# blitzbox.net
KiCad netlist of a schematic drawn in EAGLE
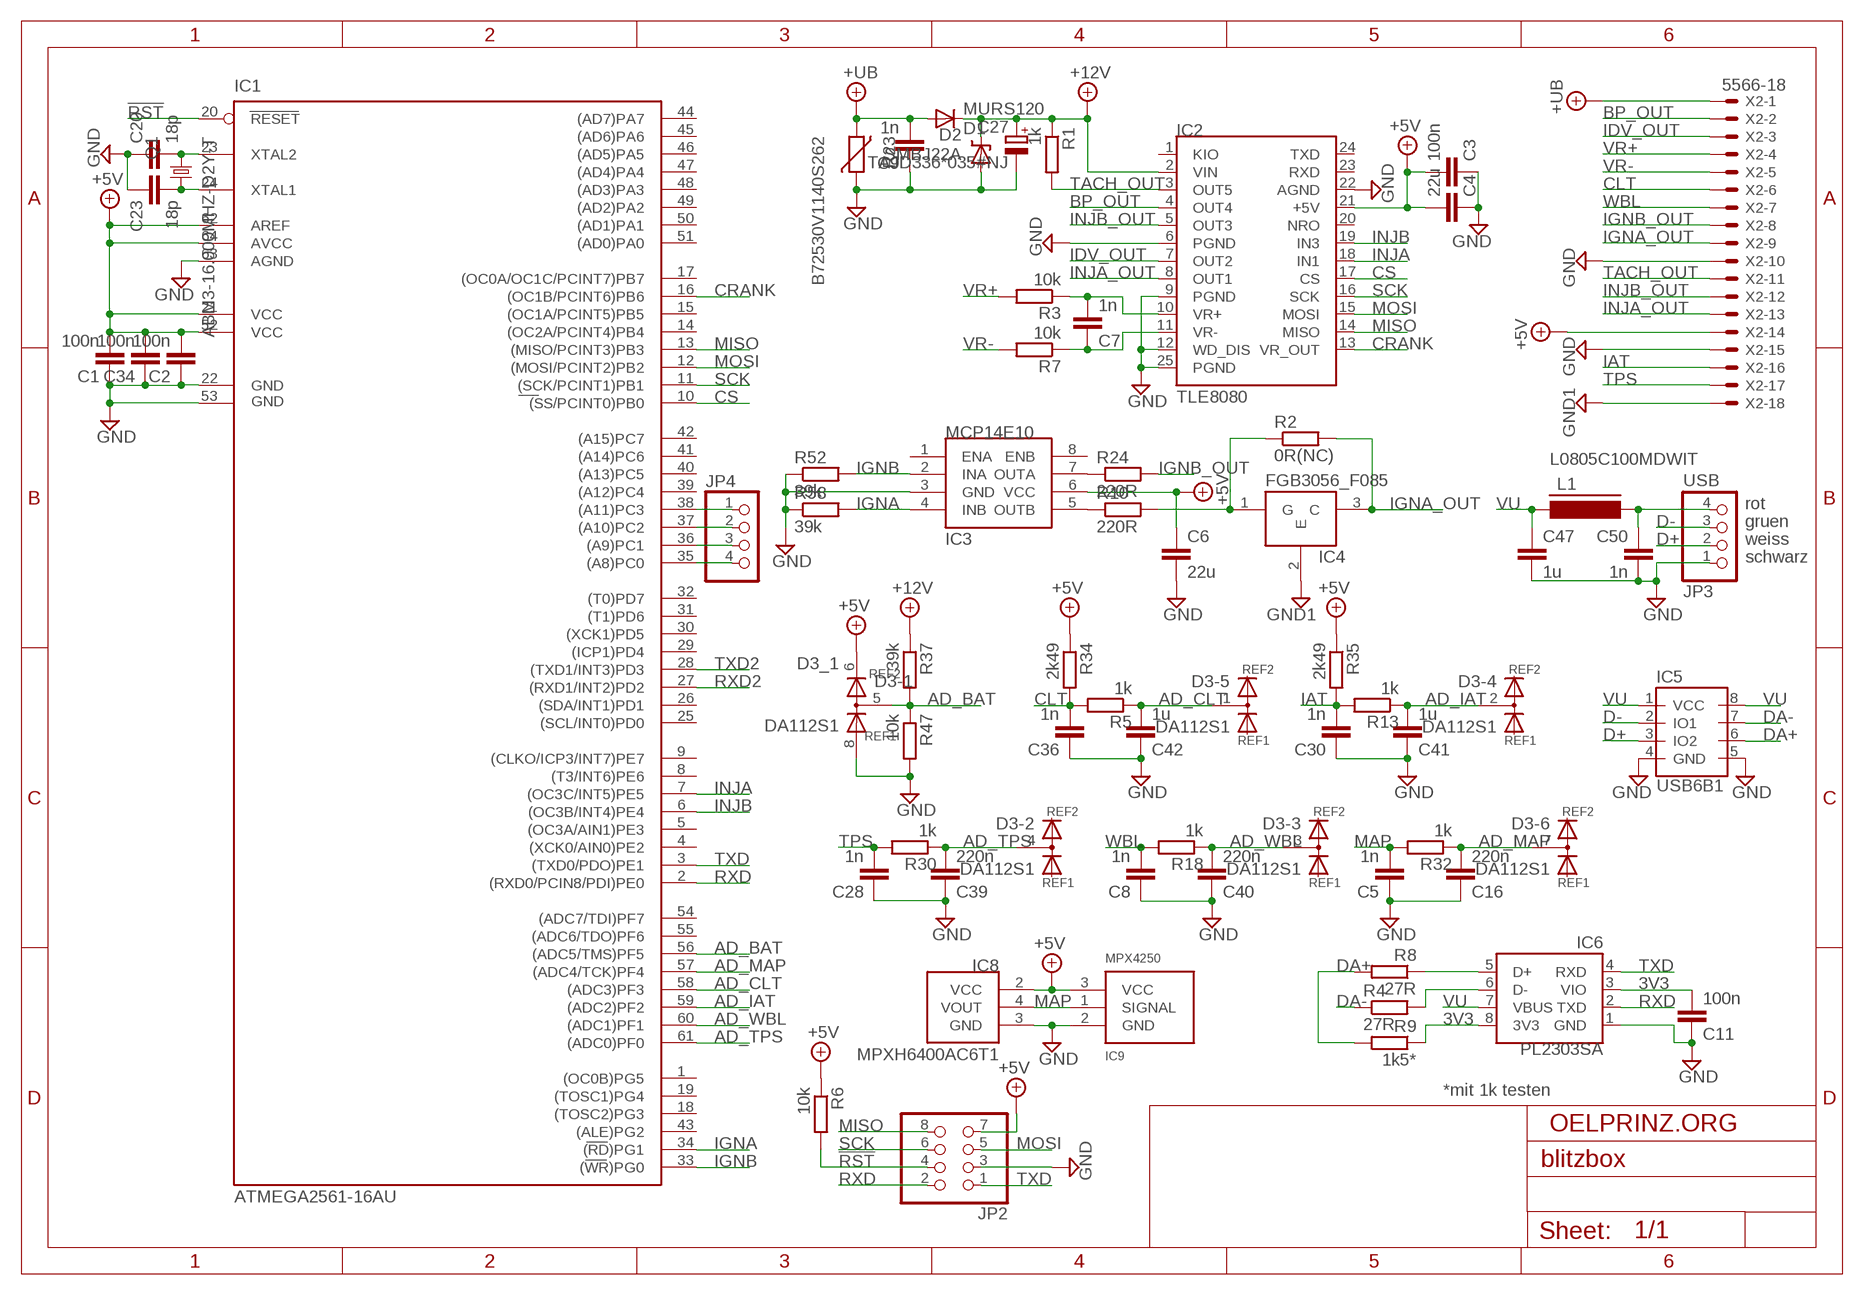
[diagram p0: schematic, sheet 1]

(export (version "E")
  (design (tool "Eeschema 10.0.6"))
  (components
    (comp (ref "C1")
      (value "100n")
      (footprint "eagle-import:C0805")
      (libsource (lib "eagle-import") (part "C-EUC0805"))
    )
    (comp (ref "C2")
      (value "100n")
      (footprint "eagle-import:C0805")
      (libsource (lib "eagle-import") (part "C-EUC0805"))
    )
    (comp (ref "C3")
      (value "100n")
      (footprint "eagle-import:C0805")
      (libsource (lib "eagle-import") (part "C-EUC0805"))
    )
    (comp (ref "C4")
      (value "22u")
      (footprint "eagle-import:C1210")
      (libsource (lib "eagle-import") (part "C-EUC1210"))
    )
    (comp (ref "C5")
      (value "1n")
      (footprint "eagle-import:C0805")
      (libsource (lib "eagle-import") (part "C-EUC0805"))
    )
    (comp (ref "C6")
      (value "22u")
      (footprint "eagle-import:C1206")
      (libsource (lib "eagle-import") (part "C-EUC1206"))
    )
    (comp (ref "C7")
      (value "1n")
      (footprint "eagle-import:C0805")
      (libsource (lib "eagle-import") (part "C-EUC0805"))
    )
    (comp (ref "C8")
      (value "1n")
      (footprint "eagle-import:C0805")
      (libsource (lib "eagle-import") (part "C-EUC0805"))
    )
    (comp (ref "C9")
      (value "1n")
      (footprint "eagle-import:C0805")
      (libsource (lib "eagle-import") (part "C-EUC0805"))
    )
    (comp (ref "C11")
      (value "100n")
      (footprint "eagle-import:C0805")
      (libsource (lib "eagle-import") (part "C-EUC0805"))
    )
    (comp (ref "C16")
      (value "220n")
      (footprint "eagle-import:C0805")
      (libsource (lib "eagle-import") (part "C-EUC0805"))
    )
    (comp (ref "C20")
      (value "18p")
      (footprint "eagle-import:C0805")
      (libsource (lib "eagle-import") (part "C-EUC0805"))
    )
    (comp (ref "C23")
      (value "18p")
      (footprint "eagle-import:C0805")
      (libsource (lib "eagle-import") (part "C-EUC0805"))
    )
    (comp (ref "C27")
      (value "TAJD336*035#NJ")
      (footprint "eagle-import:SMC_D")
      (libsource (lib "eagle-import") (part "CPOL-EUSMCD"))
    )
    (comp (ref "C28")
      (value "1n")
      (footprint "eagle-import:C0805")
      (libsource (lib "eagle-import") (part "C-EUC0805"))
    )
    (comp (ref "C30")
      (value "1n")
      (footprint "eagle-import:C0805")
      (libsource (lib "eagle-import") (part "C-EUC0805"))
    )
    (comp (ref "C34")
      (value "100n")
      (footprint "eagle-import:C0805")
      (libsource (lib "eagle-import") (part "C-EUC0805"))
    )
    (comp (ref "C36")
      (value "1n")
      (footprint "eagle-import:C0805")
      (libsource (lib "eagle-import") (part "C-EUC0805"))
    )
    (comp (ref "C39")
      (value "220n")
      (footprint "eagle-import:C0805")
      (libsource (lib "eagle-import") (part "C-EUC0805"))
    )
    (comp (ref "C40")
      (value "220n")
      (footprint "eagle-import:C0805")
      (libsource (lib "eagle-import") (part "C-EUC0805"))
    )
    (comp (ref "C41")
      (value "1u")
      (footprint "eagle-import:C0805")
      (libsource (lib "eagle-import") (part "C-EUC0805"))
    )
    (comp (ref "C42")
      (value "1u")
      (footprint "eagle-import:C0805")
      (libsource (lib "eagle-import") (part "C-EUC0805"))
    )
    (comp (ref "C47")
      (value "1u")
      (footprint "eagle-import:C0805")
      (libsource (lib "eagle-import") (part "C-EUC0805"))
    )
    (comp (ref "C50")
      (value "1n")
      (footprint "eagle-import:C0805")
      (libsource (lib "eagle-import") (part "C-EUC0805"))
    )
    (comp (ref "D1")
      (value "MURS120")
      (footprint "eagle-import:MURS120")
      (libsource (lib "eagle-import") (part "MURS120"))
    )
    (comp (ref "D2")
      (value "SMBJ22A")
      (footprint "eagle-import:SMBJ")
      (libsource (lib "eagle-import") (part "SUPPRESSOR-SMBJ"))
    )
    (comp (ref "D3")
      (value "DA112S1")
      (footprint "eagle-import:SO08")
      (fields (field (name "MF") "Arrow Electronics"))
      (libsource (lib "eagle-import") (part "DA112S1"))
    )
    (comp (ref "IC1")
      (value "ATMEGA2561-16AU")
      (footprint "eagle-import:TQFP64")
      (libsource (lib "eagle-import") (part "ATMEGA2561AU-16"))
    )
    (comp (ref "IC2")
      (value "TLE8080")
      (footprint "eagle-import:TLE8080")
      (libsource (lib "eagle-import") (part "TLE8080"))
    )
    (comp (ref "IC3")
      (value "MCP14E10")
      (footprint "eagle-import:SO-08")
      (libsource (lib "eagle-import") (part "MCP14E10"))
    )
    (comp (ref "IC4")
      (value "FGB3056_F085")
      (footprint "eagle-import:TO263")
      (libsource (lib "eagle-import") (part "FGB3056_F085"))
    )
    (comp (ref "IC5")
      (value "USB6B1")
      (footprint "eagle-import:SO08")
      (libsource (lib "eagle-import") (part "USB6B1"))
    )
    (comp (ref "IC6")
      (value "PL2303SA")
      (footprint "eagle-import:SO-08")
      (libsource (lib "eagle-import") (part "PL2303SA"))
    )
    (comp (ref "IC8")
      (value "MPXH6400AC6T1")
      (footprint "eagle-import:MPXH6400")
      (libsource (lib "eagle-import") (part "MPXH6400"))
    )
    (comp (ref "IC9")
      (value "MPX4250")
      (footprint "eagle-import:MPX4250")
      (libsource (lib "eagle-import") (part "MPX4250"))
    )
    (comp (ref "JP2")
      (value "PINHD-2X4")
      (footprint "eagle-import:2X04")
      (libsource (lib "eagle-import") (part "PINHD-2X4"))
    )
    (comp (ref "JP3")
      (value "USB")
      (footprint "eagle-import:1X04")
      (libsource (lib "eagle-import") (part "PINHD-1X4"))
    )
    (comp (ref "JP4")
      (value "PINHD-1X4")
      (footprint "eagle-import:1X04")
      (libsource (lib "eagle-import") (part "PINHD-1X4"))
    )
    (comp (ref "L1")
      (value "L0805C100MDWIT")
      (footprint "eagle-import:FB805")
      (libsource (lib "eagle-import") (part "FERRITE_BEAD805"))
    )
    (comp (ref "Q1")
      (value "ABM3-16.000MHZ-D2Y-T")
      (footprint "eagle-import:ABM3")
      (libsource (lib "eagle-import") (part "ABM3-8.000MHZ-D2Y-T"))
    )
    (comp (ref "R1")
      (value "1k")
      (footprint "eagle-import:R0805")
      (libsource (lib "eagle-import") (part "R-EU_R0805"))
    )
    (comp (ref "R2")
      (value "0R(NC)")
      (footprint "eagle-import:R0805")
      (libsource (lib "eagle-import") (part "R-EU_R0805"))
    )
    (comp (ref "R3")
      (value "10k")
      (footprint "eagle-import:R0805")
      (libsource (lib "eagle-import") (part "R-EU_R0805"))
    )
    (comp (ref "R4")
      (value "27R")
      (footprint "eagle-import:R0805")
      (libsource (lib "eagle-import") (part "R-EU_R0805"))
    )
    (comp (ref "R5")
      (value "1k")
      (footprint "eagle-import:R0805")
      (libsource (lib "eagle-import") (part "R-EU_R0805"))
    )
    (comp (ref "R6")
      (value "10k")
      (footprint "eagle-import:R0805")
      (libsource (lib "eagle-import") (part "R-EU_R0805"))
    )
    (comp (ref "R7")
      (value "10k")
      (footprint "eagle-import:R0805")
      (libsource (lib "eagle-import") (part "R-EU_R0805"))
    )
    (comp (ref "R8")
      (value "27R")
      (footprint "eagle-import:R0805")
      (libsource (lib "eagle-import") (part "R-EU_R0805"))
    )
    (comp (ref "R9")
      (value "1k5*")
      (footprint "eagle-import:R0805")
      (libsource (lib "eagle-import") (part "R-EU_R0805"))
    )
    (comp (ref "R10")
      (value "220R")
      (footprint "eagle-import:R0805")
      (libsource (lib "eagle-import") (part "R-EU_R0805"))
    )
    (comp (ref "R13")
      (value "1k")
      (footprint "eagle-import:R0805")
      (libsource (lib "eagle-import") (part "R-EU_R0805"))
    )
    (comp (ref "R18")
      (value "1k")
      (footprint "eagle-import:R0805")
      (libsource (lib "eagle-import") (part "R-EU_R0805"))
    )
    (comp (ref "R23")
      (value "B72530V1140S262")
      (footprint "eagle-import:CT_CN1210")
      (libsource (lib "eagle-import") (part "VARISTORCN1210"))
    )
    (comp (ref "R24")
      (value "220R")
      (footprint "eagle-import:R0805")
      (libsource (lib "eagle-import") (part "R-EU_R0805"))
    )
    (comp (ref "R30")
      (value "1k")
      (footprint "eagle-import:R0805")
      (libsource (lib "eagle-import") (part "R-EU_R0805"))
    )
    (comp (ref "R32")
      (value "1k")
      (footprint "eagle-import:R0805")
      (libsource (lib "eagle-import") (part "R-EU_R0805"))
    )
    (comp (ref "R34")
      (value "2k49")
      (footprint "eagle-import:R0805")
      (libsource (lib "eagle-import") (part "R-EU_R0805"))
    )
    (comp (ref "R35")
      (value "2k49")
      (footprint "eagle-import:R0805")
      (libsource (lib "eagle-import") (part "R-EU_R0805"))
    )
    (comp (ref "R37")
      (value "39k")
      (footprint "eagle-import:R0805")
      (libsource (lib "eagle-import") (part "R-EU_R0805"))
    )
    (comp (ref "R47")
      (value "10k")
      (footprint "eagle-import:R0805")
      (libsource (lib "eagle-import") (part "R-EU_R0805"))
    )
    (comp (ref "R52")
      (value "39k")
      (footprint "eagle-import:R0805")
      (libsource (lib "eagle-import") (part "R-EU_R0805"))
    )
    (comp (ref "R58")
      (value "39k")
      (footprint "eagle-import:R0805")
      (libsource (lib "eagle-import") (part "R-EU_R0805"))
    )
    (comp (ref "X2")
      (value "5566-18")
      (footprint "eagle-import:5566-18")
      (libsource (lib "eagle-import") (part "5566-18"))
    )
  )
  (nets
    (net (code "1") (name "+5V") (class "Default")
      (node (ref "C1") (pin "2") (pinfunction "2_2") (pintype "passive"))
      (node (ref "C2") (pin "2") (pinfunction "2_2") (pintype "passive"))
      (node (ref "C3") (pin "2") (pinfunction "2_2") (pintype "passive"))
      (node (ref "C34") (pin "2") (pinfunction "2_2") (pintype "passive"))
      (node (ref "C4") (pin "2") (pinfunction "2_2") (pintype "passive"))
      (node (ref "C6") (pin "1") (pinfunction "1_1") (pintype "passive"))
      (node (ref "D3") (pin "6") (pinfunction "REF2_6") (pintype "passive"))
      (node (ref "IC1") (pin "21") (pinfunction "VCC_21") (pintype "power_in"))
      (node (ref "IC1") (pin "52") (pinfunction "VCC1_52") (pintype "power_in"))
      (node (ref "IC1") (pin "62") (pinfunction "AREF_62") (pintype "bidirectional"))
      (node (ref "IC1") (pin "64") (pinfunction "AVCC_64") (pintype "power_in"))
      (node (ref "IC2") (pin "21") (pinfunction "+5V_21") (pintype "bidirectional"))
      (node (ref "IC3") (pin "6") (pinfunction "VCC_6") (pintype "bidirectional"))
      (node (ref "IC8") (pin "2") (pinfunction "VCC_2") (pintype "bidirectional"))
      (node (ref "IC9") (pin "3") (pinfunction "VCC_3") (pintype "bidirectional"))
      (node (ref "JP2") (pin "7") (pinfunction "7_7") (pintype "passive"))
      (node (ref "R34") (pin "1") (pinfunction "1_1") (pintype "passive"))
      (node (ref "R35") (pin "1") (pinfunction "1_1") (pintype "passive"))
      (node (ref "R6") (pin "1") (pinfunction "1_1") (pintype "passive"))
      (node (ref "X2") (pin "14") (pinfunction "S_14") (pintype "passive"))
    )
    (net (code "2") (name "+12V") (class "Default")
      (node (ref "C27") (pin "+") (pinfunction "+_+") (pintype "passive"))
      (node (ref "D1") (pin "2") (pinfunction "C_2") (pintype "passive"))
      (node (ref "D2") (pin "C") (pinfunction "C_C") (pintype "passive"))
      (node (ref "IC2") (pin "2") (pinfunction "VIN_2") (pintype "bidirectional"))
      (node (ref "R1") (pin "1") (pinfunction "1_1") (pintype "passive"))
      (node (ref "R37") (pin "1") (pinfunction "1_1") (pintype "passive"))
    )
    (net (code "3") (name "+UB") (class "Default")
      (node (ref "C9") (pin "2") (pinfunction "2_2") (pintype "passive"))
      (node (ref "D1") (pin "1") (pinfunction "A_1") (pintype "passive"))
      (node (ref "R23") (pin "2") (pinfunction "2_2") (pintype "passive"))
      (node (ref "X2") (pin "1") (pinfunction "S_1") (pintype "passive"))
    )
    (net (code "4") (name "/3V3") (class "Default")
      (node (ref "C11") (pin "2") (pinfunction "2_2") (pintype "passive"))
      (node (ref "IC6") (pin "3") (pinfunction "VIO_3") (pintype "bidirectional"))
      (node (ref "IC6") (pin "8") (pinfunction "3V3_8") (pintype "bidirectional"))
      (node (ref "R9") (pin "1") (pinfunction "1_1") (pintype "passive"))
    )
    (net (code "5") (name "/AD_BAT") (class "Default")
      (node (ref "D3") (pin "5") (pinfunction "K_5") (pintype "passive"))
      (node (ref "IC1") (pin "56") (pinfunction "(ADC5/TMS)PF5_56") (pintype "bidirectional"))
      (node (ref "R37") (pin "2") (pinfunction "2_2") (pintype "passive"))
      (node (ref "R47") (pin "1") (pinfunction "1_1") (pintype "passive"))
    )
    (net (code "6") (name "/AD_CLT") (class "Default")
      (node (ref "C42") (pin "2") (pinfunction "2_2") (pintype "passive"))
      (node (ref "D3") (pin "1") (pinfunction "K_1") (pintype "passive"))
      (node (ref "IC1") (pin "58") (pinfunction "(ADC3)PF3_58") (pintype "bidirectional"))
      (node (ref "R5") (pin "1") (pinfunction "1_1") (pintype "passive"))
    )
    (net (code "7") (name "/AD_IAT") (class "Default")
      (node (ref "C41") (pin "2") (pinfunction "2_2") (pintype "passive"))
      (node (ref "D3") (pin "2") (pinfunction "K_2") (pintype "passive"))
      (node (ref "IC1") (pin "59") (pinfunction "(ADC2)PF2_59") (pintype "bidirectional"))
      (node (ref "R13") (pin "1") (pinfunction "1_1") (pintype "passive"))
    )
    (net (code "8") (name "/AD_MAP") (class "Default")
      (node (ref "C16") (pin "2") (pinfunction "2_2") (pintype "passive"))
      (node (ref "D3") (pin "7") (pinfunction "K_7") (pintype "passive"))
      (node (ref "IC1") (pin "57") (pinfunction "(ADC4/TCK)PF4_57") (pintype "bidirectional"))
      (node (ref "R32") (pin "1") (pinfunction "1_1") (pintype "passive"))
    )
    (net (code "9") (name "/AD_TPS") (class "Default")
      (node (ref "C39") (pin "2") (pinfunction "2_2") (pintype "passive"))
      (node (ref "D3") (pin "4") (pinfunction "K_4") (pintype "passive"))
      (node (ref "IC1") (pin "61") (pinfunction "(ADC0)PF0_61") (pintype "bidirectional"))
      (node (ref "R30") (pin "1") (pinfunction "1_1") (pintype "passive"))
    )
    (net (code "10") (name "/AD_WBL") (class "Default")
      (node (ref "C40") (pin "2") (pinfunction "2_2") (pintype "passive"))
      (node (ref "D3") (pin "3") (pinfunction "K_3") (pintype "passive"))
      (node (ref "IC1") (pin "60") (pinfunction "(ADC1)PF1_60") (pintype "bidirectional"))
      (node (ref "R18") (pin "1") (pinfunction "1_1") (pintype "passive"))
    )
    (net (code "11") (name "/BP_OUT") (class "Default")
      (node (ref "IC2") (pin "4") (pinfunction "OUT4_4") (pintype "bidirectional"))
      (node (ref "X2") (pin "2") (pinfunction "S_2") (pintype "passive"))
    )
    (net (code "12") (name "/CLT") (class "Default")
      (node (ref "C36") (pin "2") (pinfunction "2_2") (pintype "passive"))
      (node (ref "R34") (pin "2") (pinfunction "2_2") (pintype "passive"))
      (node (ref "R5") (pin "2") (pinfunction "2_2") (pintype "passive"))
      (node (ref "X2") (pin "6") (pinfunction "S_6") (pintype "passive"))
    )
    (net (code "13") (name "/CRANK") (class "Default")
      (node (ref "IC1") (pin "16") (pinfunction "(OC1B/PCINT6)PB6_16") (pintype "bidirectional"))
      (node (ref "IC2") (pin "13") (pinfunction "VR_OUT_13") (pintype "bidirectional"))
    )
    (net (code "14") (name "/CS") (class "Default")
      (node (ref "IC1") (pin "10") (pinfunction "(SS/PCINT0)PB0_10") (pintype "bidirectional"))
      (node (ref "IC2") (pin "17") (pinfunction "CS_17") (pintype "bidirectional"))
    )
    (net (code "15") (name "/D+") (class "Default")
      (node (ref "IC5") (pin "3") (pinfunction "IO2_3") (pintype "bidirectional"))
      (node (ref "JP3") (pin "2") (pinfunction "2_2") (pintype "passive"))
    )
    (net (code "16") (name "/D-") (class "Default")
      (node (ref "IC5") (pin "2") (pinfunction "IO1_2") (pintype "bidirectional"))
      (node (ref "JP3") (pin "3") (pinfunction "3_3") (pintype "passive"))
    )
    (net (code "17") (name "/DA+") (class "Default")
      (node (ref "IC5") (pin "6") (pinfunction "IO2_6") (pintype "bidirectional"))
      (node (ref "R8") (pin "2") (pinfunction "2_2") (pintype "passive"))
      (node (ref "R9") (pin "2") (pinfunction "2_2") (pintype "passive"))
    )
    (net (code "18") (name "/DA-") (class "Default")
      (node (ref "IC5") (pin "7") (pinfunction "IO1_7") (pintype "bidirectional"))
      (node (ref "R4") (pin "1") (pinfunction "1_1") (pintype "passive"))
    )
    (net (code "19") (name "/IAT") (class "Default")
      (node (ref "C30") (pin "2") (pinfunction "2_2") (pintype "passive"))
      (node (ref "R13") (pin "2") (pinfunction "2_2") (pintype "passive"))
      (node (ref "R35") (pin "2") (pinfunction "2_2") (pintype "passive"))
      (node (ref "X2") (pin "16") (pinfunction "S_16") (pintype "passive"))
    )
    (net (code "20") (name "/IDV_OUT") (class "Default")
      (node (ref "IC2") (pin "7") (pinfunction "OUT2_7") (pintype "bidirectional"))
      (node (ref "X2") (pin "3") (pinfunction "S_3") (pintype "passive"))
    )
    (net (code "21") (name "/IGNA") (class "Default")
      (node (ref "IC1") (pin "34") (pinfunction "(RD)PG1_34") (pintype "bidirectional"))
      (node (ref "IC3") (pin "4") (pinfunction "INB_4") (pintype "bidirectional"))
      (node (ref "R58") (pin "2") (pinfunction "2_2") (pintype "passive"))
    )
    (net (code "22") (name "/IGNA_OUT") (class "Default")
      (node (ref "IC4") (pin "3") (pinfunction "C_3") (pintype "bidirectional"))
      (node (ref "R2") (pin "2") (pinfunction "2_2") (pintype "passive"))
      (node (ref "X2") (pin "9") (pinfunction "S_9") (pintype "passive"))
    )
    (net (code "23") (name "/IGNB") (class "Default")
      (node (ref "IC1") (pin "33") (pinfunction "(WR)PG0_33") (pintype "bidirectional"))
      (node (ref "IC3") (pin "2") (pinfunction "INA_2") (pintype "bidirectional"))
      (node (ref "R52") (pin "2") (pinfunction "2_2") (pintype "passive"))
    )
    (net (code "24") (name "/IGNB_OUT") (class "Default")
      (node (ref "R24") (pin "2") (pinfunction "2_2") (pintype "passive"))
      (node (ref "X2") (pin "8") (pinfunction "S_8") (pintype "passive"))
    )
    (net (code "25") (name "/INJA") (class "Default")
      (node (ref "IC1") (pin "7") (pinfunction "(OC3C/INT5)PE5_7") (pintype "bidirectional"))
      (node (ref "IC2") (pin "18") (pinfunction "IN1_18") (pintype "bidirectional"))
    )
    (net (code "26") (name "/INJA_OUT") (class "Default")
      (node (ref "IC2") (pin "8") (pinfunction "OUT1_8") (pintype "bidirectional"))
      (node (ref "X2") (pin "13") (pinfunction "S_13") (pintype "passive"))
    )
    (net (code "27") (name "/INJB") (class "Default")
      (node (ref "IC1") (pin "6") (pinfunction "(OC3B/INT4)PE4_6") (pintype "bidirectional"))
      (node (ref "IC2") (pin "19") (pinfunction "IN3_19") (pintype "bidirectional"))
    )
    (net (code "28") (name "/INJB_OUT") (class "Default")
      (node (ref "IC2") (pin "5") (pinfunction "OUT3_5") (pintype "bidirectional"))
      (node (ref "X2") (pin "12") (pinfunction "S_12") (pintype "passive"))
    )
    (net (code "29") (name "/MAP") (class "Default")
      (node (ref "C5") (pin "2") (pinfunction "2_2") (pintype "passive"))
      (node (ref "IC8") (pin "4") (pinfunction "VOUT_4") (pintype "bidirectional"))
      (node (ref "IC9") (pin "1") (pinfunction "SIGNAL_1") (pintype "bidirectional"))
      (node (ref "R32") (pin "2") (pinfunction "2_2") (pintype "passive"))
    )
    (net (code "30") (name "/MISO") (class "Default")
      (node (ref "IC1") (pin "13") (pinfunction "(MISO/PCINT3)PB3_13") (pintype "bidirectional"))
      (node (ref "IC2") (pin "14") (pinfunction "MISO_14") (pintype "bidirectional"))
      (node (ref "JP2") (pin "8") (pinfunction "8_8") (pintype "passive"))
    )
    (net (code "31") (name "/MOSI") (class "Default")
      (node (ref "IC1") (pin "12") (pinfunction "(MOSI/PCINT2)PB2_12") (pintype "bidirectional"))
      (node (ref "IC2") (pin "15") (pinfunction "MOSI_15") (pintype "bidirectional"))
      (node (ref "JP2") (pin "5") (pinfunction "5_5") (pintype "passive"))
    )
    (net (code "32") (name "/RXD") (class "Default")
      (node (ref "IC1") (pin "2") (pinfunction "(RXD0/PCIN8/PDI)PE0_2") (pintype "bidirectional"))
      (node (ref "IC6") (pin "2") (pinfunction "TXD_2") (pintype "bidirectional"))
      (node (ref "JP2") (pin "2") (pinfunction "2_2") (pintype "passive"))
    )
    (net (code "33") (name "/RXD2") (class "Default")
      (node (ref "IC1") (pin "27") (pinfunction "(RXD1/INT2)PD2_27") (pintype "bidirectional"))
    )
    (net (code "34") (name "/SCK") (class "Default")
      (node (ref "IC1") (pin "11") (pinfunction "(SCK/PCINT1)PB1_11") (pintype "bidirectional"))
      (node (ref "IC2") (pin "16") (pinfunction "SCK_16") (pintype "bidirectional"))
      (node (ref "JP2") (pin "6") (pinfunction "6_6") (pintype "passive"))
    )
    (net (code "35") (name "/TACH_OUT") (class "Default")
      (node (ref "IC2") (pin "3") (pinfunction "OUT5_3") (pintype "bidirectional"))
      (node (ref "R1") (pin "2") (pinfunction "2_2") (pintype "passive"))
      (node (ref "X2") (pin "11") (pinfunction "S_11") (pintype "passive"))
    )
    (net (code "36") (name "/TPS") (class "Default")
      (node (ref "C28") (pin "2") (pinfunction "2_2") (pintype "passive"))
      (node (ref "R30") (pin "2") (pinfunction "2_2") (pintype "passive"))
      (node (ref "X2") (pin "17") (pinfunction "S_17") (pintype "passive"))
    )
    (net (code "37") (name "/TXD") (class "Default")
      (node (ref "IC1") (pin "3") (pinfunction "(TXD0/PDO)PE1_3") (pintype "bidirectional"))
      (node (ref "IC6") (pin "4") (pinfunction "RXD_4") (pintype "bidirectional"))
      (node (ref "JP2") (pin "1") (pinfunction "1_1") (pintype "passive"))
    )
    (net (code "38") (name "/TXD2") (class "Default")
      (node (ref "IC1") (pin "28") (pinfunction "(TXD1/INT3)PD3_28") (pintype "bidirectional"))
    )
    (net (code "39") (name "/VR+") (class "Default")
      (node (ref "R3") (pin "2") (pinfunction "2_2") (pintype "passive"))
      (node (ref "X2") (pin "4") (pinfunction "S_4") (pintype "passive"))
    )
    (net (code "40") (name "/VR-") (class "Default")
      (node (ref "R7") (pin "2") (pinfunction "2_2") (pintype "passive"))
      (node (ref "X2") (pin "5") (pinfunction "S_5") (pintype "passive"))
    )
    (net (code "41") (name "/VU") (class "Default")
      (node (ref "C47") (pin "1") (pinfunction "1_1") (pintype "passive"))
      (node (ref "IC5") (pin "1") (pinfunction "VCC_1") (pintype "power_in"))
      (node (ref "IC5") (pin "8") (pinfunction "VCC_8") (pintype "power_in"))
      (node (ref "IC6") (pin "7") (pinfunction "VBUS_7") (pintype "bidirectional"))
      (node (ref "L1") (pin "1") (pinfunction "1_1") (pintype "passive"))
    )
    (net (code "42") (name "/WBL") (class "Default")
      (node (ref "C8") (pin "2") (pinfunction "2_2") (pintype "passive"))
      (node (ref "R18") (pin "2") (pinfunction "2_2") (pintype "passive"))
      (node (ref "X2") (pin "7") (pinfunction "S_7") (pintype "passive"))
    )
    (net (code "43") (name "/~{RST}") (class "Default")
      (node (ref "IC1") (pin "20") (pinfunction "RESET_20") (pintype "input"))
      (node (ref "JP2") (pin "4") (pinfunction "4_4") (pintype "passive"))
      (node (ref "R6") (pin "2") (pinfunction "2_2") (pintype "passive"))
    )
    (net (code "44") (name "GND") (class "Default")
      (node (ref "C1") (pin "1") (pinfunction "1_1") (pintype "passive"))
      (node (ref "C11") (pin "1") (pinfunction "1_1") (pintype "passive"))
      (node (ref "C16") (pin "1") (pinfunction "1_1") (pintype "passive"))
      (node (ref "C2") (pin "1") (pinfunction "1_1") (pintype "passive"))
      (node (ref "C20") (pin "1") (pinfunction "1_1") (pintype "passive"))
      (node (ref "C23") (pin "1") (pinfunction "1_1") (pintype "passive"))
      (node (ref "C27") (pin "-") (pinfunction "-_-") (pintype "passive"))
      (node (ref "C28") (pin "1") (pinfunction "1_1") (pintype "passive"))
      (node (ref "C3") (pin "1") (pinfunction "1_1") (pintype "passive"))
      (node (ref "C30") (pin "1") (pinfunction "1_1") (pintype "passive"))
      (node (ref "C34") (pin "1") (pinfunction "1_1") (pintype "passive"))
      (node (ref "C36") (pin "1") (pinfunction "1_1") (pintype "passive"))
      (node (ref "C39") (pin "1") (pinfunction "1_1") (pintype "passive"))
      (node (ref "C4") (pin "1") (pinfunction "1_1") (pintype "passive"))
      (node (ref "C40") (pin "1") (pinfunction "1_1") (pintype "passive"))
      (node (ref "C41") (pin "1") (pinfunction "1_1") (pintype "passive"))
      (node (ref "C42") (pin "1") (pinfunction "1_1") (pintype "passive"))
      (node (ref "C47") (pin "2") (pinfunction "2_2") (pintype "passive"))
      (node (ref "C5") (pin "1") (pinfunction "1_1") (pintype "passive"))
      (node (ref "C50") (pin "2") (pinfunction "2_2") (pintype "passive"))
      (node (ref "C6") (pin "2") (pinfunction "2_2") (pintype "passive"))
      (node (ref "C8") (pin "1") (pinfunction "1_1") (pintype "passive"))
      (node (ref "C9") (pin "1") (pinfunction "1_1") (pintype "passive"))
      (node (ref "D2") (pin "A") (pinfunction "A_A") (pintype "passive"))
      (node (ref "D3") (pin "8") (pinfunction "REF1_8") (pintype "passive"))
      (node (ref "IC1") (pin "22") (pinfunction "GND_22") (pintype "power_in"))
      (node (ref "IC1") (pin "53") (pinfunction "GND1_53") (pintype "power_in"))
      (node (ref "IC1") (pin "63") (pinfunction "AGND_63") (pintype "power_in"))
      (node (ref "IC2") (pin "12") (pinfunction "WD_DIS_12") (pintype "bidirectional"))
      (node (ref "IC2") (pin "22") (pinfunction "AGND_22") (pintype "bidirectional"))
      (node (ref "IC2") (pin "25") (pinfunction "PGND_25") (pintype "bidirectional"))
      (node (ref "IC2") (pin "6") (pinfunction "PGND_6") (pintype "bidirectional"))
      (node (ref "IC2") (pin "9") (pinfunction "PGND_9") (pintype "bidirectional"))
      (node (ref "IC3") (pin "3") (pinfunction "GND_3") (pintype "bidirectional"))
      (node (ref "IC5") (pin "4") (pinfunction "GND_4") (pintype "power_in"))
      (node (ref "IC5") (pin "5") (pinfunction "GND_5") (pintype "power_in"))
      (node (ref "IC6") (pin "1") (pinfunction "GND_1") (pintype "bidirectional"))
      (node (ref "IC8") (pin "3") (pinfunction "GND_3") (pintype "bidirectional"))
      (node (ref "IC9") (pin "2") (pinfunction "GND_2") (pintype "bidirectional"))
      (node (ref "JP2") (pin "3") (pinfunction "3_3") (pintype "passive"))
      (node (ref "JP3") (pin "1") (pinfunction "1_1") (pintype "passive"))
      (node (ref "R23") (pin "1") (pinfunction "1_1") (pintype "passive"))
      (node (ref "R47") (pin "2") (pinfunction "2_2") (pintype "passive"))
      (node (ref "R52") (pin "1") (pinfunction "1_1") (pintype "passive"))
      (node (ref "R58") (pin "1") (pinfunction "1_1") (pintype "passive"))
      (node (ref "X2") (pin "10") (pinfunction "S_10") (pintype "passive"))
      (node (ref "X2") (pin "15") (pinfunction "S_15") (pintype "passive"))
    )
    (net (code "45") (name "GND1") (class "Default")
      (node (ref "IC4") (pin "2") (pinfunction "E_2") (pintype "bidirectional"))
      (node (ref "X2") (pin "18") (pinfunction "S_18") (pintype "passive"))
    )
    (net (code "46") (name "Net-(C50-Pad1)") (class "Default")
      (node (ref "C50") (pin "1") (pinfunction "1_1") (pintype "passive"))
      (node (ref "JP3") (pin "4") (pinfunction "4_4") (pintype "passive"))
      (node (ref "L1") (pin "2") (pinfunction "2_2") (pintype "passive"))
    )
    (net (code "47") (name "Net-(IC1-(A8)PC0)") (class "Default")
      (node (ref "IC1") (pin "35") (pinfunction "(A8)PC0_35") (pintype "bidirectional"))
      (node (ref "JP4") (pin "4") (pinfunction "4_4") (pintype "passive"))
    )
    (net (code "48") (name "Net-(IC1-(A9)PC1)") (class "Default")
      (node (ref "IC1") (pin "36") (pinfunction "(A9)PC1_36") (pintype "bidirectional"))
      (node (ref "JP4") (pin "3") (pinfunction "3_3") (pintype "passive"))
    )
    (net (code "49") (name "Net-(IC1-(A10)PC2)") (class "Default")
      (node (ref "IC1") (pin "37") (pinfunction "(A10)PC2_37") (pintype "bidirectional"))
      (node (ref "JP4") (pin "2") (pinfunction "2_2") (pintype "passive"))
    )
    (net (code "50") (name "Net-(IC1-(A11)PC3)") (class "Default")
      (node (ref "IC1") (pin "38") (pinfunction "(A11)PC3_38") (pintype "bidirectional"))
      (node (ref "JP4") (pin "1") (pinfunction "1_1") (pintype "passive"))
    )
    (net (code "51") (name "Net-(IC1-XTAL1)") (class "Default")
      (node (ref "C23") (pin "2") (pinfunction "2_2") (pintype "passive"))
      (node (ref "IC1") (pin "24") (pinfunction "XTAL1_24") (pintype "input"))
      (node (ref "Q1") (pin "2") (pinfunction "2_2") (pintype "bidirectional"))
    )
    (net (code "52") (name "Net-(IC1-XTAL2)") (class "Default")
      (node (ref "C20") (pin "2") (pinfunction "2_2") (pintype "passive"))
      (node (ref "IC1") (pin "23") (pinfunction "XTAL2_23") (pintype "output"))
      (node (ref "Q1") (pin "1") (pinfunction "1_1") (pintype "bidirectional"))
    )
    (net (code "53") (name "Net-(IC2-VR+)") (class "Default")
      (node (ref "C7") (pin "2") (pinfunction "2_2") (pintype "passive"))
      (node (ref "IC2") (pin "10") (pinfunction "VR+_10") (pintype "bidirectional"))
      (node (ref "R3") (pin "1") (pinfunction "1_1") (pintype "passive"))
    )
    (net (code "54") (name "Net-(IC2-VR-)") (class "Default")
      (node (ref "C7") (pin "1") (pinfunction "1_1") (pintype "passive"))
      (node (ref "IC2") (pin "11") (pinfunction "VR-_11") (pintype "bidirectional"))
      (node (ref "R7") (pin "1") (pinfunction "1_1") (pintype "passive"))
    )
    (net (code "55") (name "Net-(IC3-OUTA)") (class "Default")
      (node (ref "IC3") (pin "7") (pinfunction "OUTA_7") (pintype "bidirectional"))
      (node (ref "R24") (pin "1") (pinfunction "1_1") (pintype "passive"))
    )
    (net (code "56") (name "Net-(IC3-OUTB)") (class "Default")
      (node (ref "IC3") (pin "5") (pinfunction "OUTB_5") (pintype "bidirectional"))
      (node (ref "R10") (pin "1") (pinfunction "1_1") (pintype "passive"))
    )
    (net (code "57") (name "Net-(IC4-G)") (class "Default")
      (node (ref "IC4") (pin "1") (pinfunction "G_1") (pintype "bidirectional"))
      (node (ref "R10") (pin "2") (pinfunction "2_2") (pintype "passive"))
      (node (ref "R2") (pin "1") (pinfunction "1_1") (pintype "passive"))
    )
    (net (code "58") (name "Net-(IC6-D+)") (class "Default")
      (node (ref "IC6") (pin "5") (pinfunction "D+_5") (pintype "bidirectional"))
      (node (ref "R8") (pin "1") (pinfunction "1_1") (pintype "passive"))
    )
    (net (code "59") (name "Net-(IC6-D-)") (class "Default")
      (node (ref "IC6") (pin "6") (pinfunction "D-_6") (pintype "bidirectional"))
      (node (ref "R4") (pin "2") (pinfunction "2_2") (pintype "passive"))
    )
    (net (code "60") (name "unconnected-(IC1-(A12)PC4-Pad39)") (class "Default")
      (node (ref "IC1") (pin "39") (pinfunction "(A12)PC4_39") (pintype "bidirectional"))
    )
    (net (code "61") (name "unconnected-(IC1-(A13)PC5-Pad40)") (class "Default")
      (node (ref "IC1") (pin "40") (pinfunction "(A13)PC5_40") (pintype "bidirectional"))
    )
    (net (code "62") (name "unconnected-(IC1-(A14)PC6-Pad41)") (class "Default")
      (node (ref "IC1") (pin "41") (pinfunction "(A14)PC6_41") (pintype "bidirectional"))
    )
    (net (code "63") (name "unconnected-(IC1-(A15)PC7-Pad42)") (class "Default")
      (node (ref "IC1") (pin "42") (pinfunction "(A15)PC7_42") (pintype "bidirectional"))
    )
    (net (code "64") (name "unconnected-(IC1-(AD0)PA0-Pad51)") (class "Default")
      (node (ref "IC1") (pin "51") (pinfunction "(AD0)PA0_51") (pintype "bidirectional"))
    )
    (net (code "65") (name "unconnected-(IC1-(AD1)PA1-Pad50)") (class "Default")
      (node (ref "IC1") (pin "50") (pinfunction "(AD1)PA1_50") (pintype "bidirectional"))
    )
    (net (code "66") (name "unconnected-(IC1-(AD2)PA2-Pad49)") (class "Default")
      (node (ref "IC1") (pin "49") (pinfunction "(AD2)PA2_49") (pintype "bidirectional"))
    )
    (net (code "67") (name "unconnected-(IC1-(AD3)PA3-Pad48)") (class "Default")
      (node (ref "IC1") (pin "48") (pinfunction "(AD3)PA3_48") (pintype "bidirectional"))
    )
    (net (code "68") (name "unconnected-(IC1-(AD4)PA4-Pad47)") (class "Default")
      (node (ref "IC1") (pin "47") (pinfunction "(AD4)PA4_47") (pintype "bidirectional"))
    )
    (net (code "69") (name "unconnected-(IC1-(AD5)PA5-Pad46)") (class "Default")
      (node (ref "IC1") (pin "46") (pinfunction "(AD5)PA5_46") (pintype "bidirectional"))
    )
    (net (code "70") (name "unconnected-(IC1-(AD6)PA6-Pad45)") (class "Default")
      (node (ref "IC1") (pin "45") (pinfunction "(AD6)PA6_45") (pintype "bidirectional"))
    )
    (net (code "71") (name "unconnected-(IC1-(AD7)PA7-Pad44)") (class "Default")
      (node (ref "IC1") (pin "44") (pinfunction "(AD7)PA7_44") (pintype "bidirectional"))
    )
    (net (code "72") (name "unconnected-(IC1-(ADC6{slash}TDO)PF6-Pad55)") (class "Default")
      (node (ref "IC1") (pin "55") (pinfunction "(ADC6/TDO)PF6_55") (pintype "bidirectional"))
    )
    (net (code "73") (name "unconnected-(IC1-(ADC7{slash}TDI)PF7-Pad54)") (class "Default")
      (node (ref "IC1") (pin "54") (pinfunction "(ADC7/TDI)PF7_54") (pintype "bidirectional"))
    )
    (net (code "74") (name "unconnected-(IC1-(ALE)PG2-Pad43)") (class "Default")
      (node (ref "IC1") (pin "43") (pinfunction "(ALE)PG2_43") (pintype "bidirectional"))
    )
    (net (code "75") (name "unconnected-(IC1-(CLKO{slash}ICP3{slash}INT7)PE7-Pad9)") (class "Default")
      (node (ref "IC1") (pin "9") (pinfunction "(CLKO/ICP3/INT7)PE7_9") (pintype "bidirectional"))
    )
    (net (code "76") (name "unconnected-(IC1-(ICP1)PD4-Pad29)") (class "Default")
      (node (ref "IC1") (pin "29") (pinfunction "(ICP1)PD4_29") (pintype "bidirectional"))
    )
    (net (code "77") (name "unconnected-(IC1-(OC0A{slash}OC1C{slash}PCINT7)PB7-Pad17)") (class "Default")
      (node (ref "IC1") (pin "17") (pinfunction "(OC0A/OC1C/PCINT7)PB7_17") (pintype "bidirectional"))
    )
    (net (code "78") (name "unconnected-(IC1-(OC0B)PG5-Pad1)") (class "Default")
      (node (ref "IC1") (pin "1") (pinfunction "(OC0B)PG5_1") (pintype "bidirectional"))
    )
    (net (code "79") (name "unconnected-(IC1-(OC1A{slash}PCINT5)PB5-Pad15)") (class "Default")
      (node (ref "IC1") (pin "15") (pinfunction "(OC1A/PCINT5)PB5_15") (pintype "bidirectional"))
    )
    (net (code "80") (name "unconnected-(IC1-(OC2A{slash}PCINT4)PB4-Pad14)") (class "Default")
      (node (ref "IC1") (pin "14") (pinfunction "(OC2A/PCINT4)PB4_14") (pintype "bidirectional"))
    )
    (net (code "81") (name "unconnected-(IC1-(OC3A{slash}AIN1)PE3-Pad5)") (class "Default")
      (node (ref "IC1") (pin "5") (pinfunction "(OC3A/AIN1)PE3_5") (pintype "bidirectional"))
    )
    (net (code "82") (name "unconnected-(IC1-(SCL{slash}INT0)PD0-Pad25)") (class "Default")
      (node (ref "IC1") (pin "25") (pinfunction "(SCL/INT0)PD0_25") (pintype "bidirectional"))
    )
    (net (code "83") (name "unconnected-(IC1-(SDA{slash}INT1)PD1-Pad26)") (class "Default")
      (node (ref "IC1") (pin "26") (pinfunction "(SDA/INT1)PD1_26") (pintype "bidirectional"))
    )
    (net (code "84") (name "unconnected-(IC1-(T0)PD7-Pad32)") (class "Default")
      (node (ref "IC1") (pin "32") (pinfunction "(T0)PD7_32") (pintype "bidirectional"))
    )
    (net (code "85") (name "unconnected-(IC1-(T1)PD6-Pad31)") (class "Default")
      (node (ref "IC1") (pin "31") (pinfunction "(T1)PD6_31") (pintype "bidirectional"))
    )
    (net (code "86") (name "unconnected-(IC1-(T3{slash}INT6)PE6-Pad8)") (class "Default")
      (node (ref "IC1") (pin "8") (pinfunction "(T3/INT6)PE6_8") (pintype "bidirectional"))
    )
    (net (code "87") (name "unconnected-(IC1-(TOSC1)PG4-Pad19)") (class "Default")
      (node (ref "IC1") (pin "19") (pinfunction "(TOSC1)PG4_19") (pintype "bidirectional"))
    )
    (net (code "88") (name "unconnected-(IC1-(TOSC2)PG3-Pad18)") (class "Default")
      (node (ref "IC1") (pin "18") (pinfunction "(TOSC2)PG3_18") (pintype "bidirectional"))
    )
    (net (code "89") (name "unconnected-(IC1-(XCK0{slash}AIN0)PE2-Pad4)") (class "Default")
      (node (ref "IC1") (pin "4") (pinfunction "(XCK0/AIN0)PE2_4") (pintype "bidirectional"))
    )
    (net (code "90") (name "unconnected-(IC1-(XCK1)PD5-Pad30)") (class "Default")
      (node (ref "IC1") (pin "30") (pinfunction "(XCK1)PD5_30") (pintype "bidirectional"))
    )
    (net (code "91") (name "unconnected-(IC2-KIO-Pad1)") (class "Default")
      (node (ref "IC2") (pin "1") (pinfunction "KIO_1") (pintype "bidirectional"))
    )
    (net (code "92") (name "unconnected-(IC2-NRO-Pad20)") (class "Default")
      (node (ref "IC2") (pin "20") (pinfunction "NRO_20") (pintype "bidirectional"))
    )
    (net (code "93") (name "unconnected-(IC2-RXD-Pad23)") (class "Default")
      (node (ref "IC2") (pin "23") (pinfunction "RXD_23") (pintype "bidirectional"))
    )
    (net (code "94") (name "unconnected-(IC2-TXD-Pad24)") (class "Default")
      (node (ref "IC2") (pin "24") (pinfunction "TXD_24") (pintype "bidirectional"))
    )
    (net (code "95") (name "unconnected-(IC3-ENA-Pad1)") (class "Default")
      (node (ref "IC3") (pin "1") (pinfunction "ENA_1") (pintype "bidirectional"))
    )
    (net (code "96") (name "unconnected-(IC3-ENB-Pad8)") (class "Default")
      (node (ref "IC3") (pin "8") (pinfunction "ENB_8") (pintype "bidirectional"))
    )
  )
)
